# uduino-v1_1.net
KiCad netlist of a schematic drawn in EAGLE
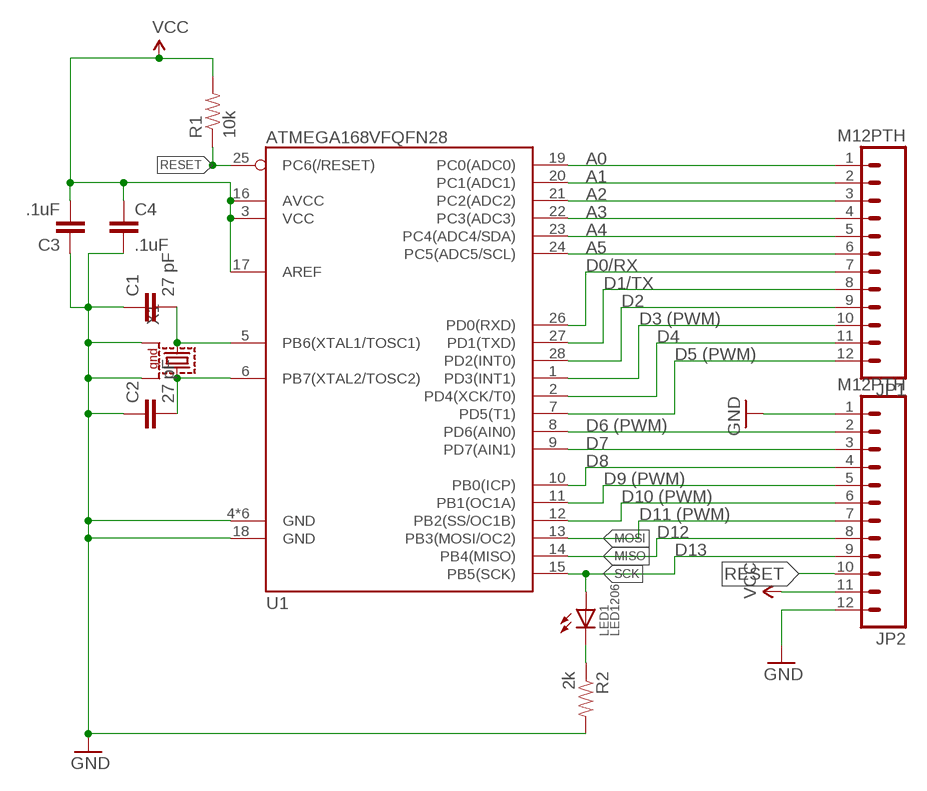
[diagram p0: schematic, sheet 1]

(export (version "E")
  (design (tool "Eeschema 10.0.6"))
  (components
    (comp (ref "C1")
      (value "27 pF")
      (footprint "eagle-import:CAP-0603")
      (libsource (lib "eagle-import") (part "CAPCAP-0603"))
    )
    (comp (ref "C2")
      (value "27 pF")
      (footprint "eagle-import:CAP-0603")
      (libsource (lib "eagle-import") (part "CAPCAP-0603"))
    )
    (comp (ref "C3")
      (value ".1uF")
      (footprint "eagle-import:CAP-0603")
      (libsource (lib "eagle-import") (part "CAPCAP-0603"))
    )
    (comp (ref "C4")
      (value ".1uF")
      (footprint "eagle-import:CAP-0603")
      (libsource (lib "eagle-import") (part "CAPCAP-0603"))
    )
    (comp (ref "JP1")
      (value "M12PTH")
      (footprint "eagle-import:1X12")
      (libsource (lib "eagle-import") (part "M12PTH"))
    )
    (comp (ref "JP2")
      (value "M12PTH")
      (footprint "eagle-import:1X12")
      (libsource (lib "eagle-import") (part "M12PTH"))
    )
    (comp (ref "LED1")
      (value "LED1206")
      (footprint "eagle-import:LED-1206")
      (libsource (lib "eagle-import") (part "LED1206"))
    )
    (comp (ref "R1")
      (value "10k")
      (footprint "eagle-import:RES-0603")
      (libsource (lib "eagle-import") (part "RESISTOR0603"))
    )
    (comp (ref "R2")
      (value "2k")
      (footprint "eagle-import:RES-0603")
      (libsource (lib "eagle-import") (part "RESISTOR0603"))
    )
    (comp (ref "U1")
      (value "ATMEGA168VFQFN28")
      (footprint "eagle-import:VQFN28")
      (libsource (lib "eagle-import") (part "ATMEGA168-28PINVFQFN-28"))
    )
    (comp (ref "X1")
      (value "CRYSTAL-SMD-7B-SERIES-TXC")
      (footprint "eagle-import:CRYSTAL-SMD-7B-SERIES-5X3.2MM")
      (fields (field (name "MFG") "TXC") (field (name "MPN") "7B SERIES"))
      (libsource (lib "eagle-import") (part "CRYSTAL-SMD-7B-SERIES-TXC"))
    )
  )
  (nets
    (net (code "1") (name "GND") (class "Default")
      (node (ref "C1") (pin "1") (pinfunction "1_1") (pintype "passive"))
      (node (ref "C2") (pin "1") (pinfunction "1_1") (pintype "passive"))
      (node (ref "C3") (pin "1") (pinfunction "1_1") (pintype "passive"))
      (node (ref "C4") (pin "2") (pinfunction "2_2") (pintype "passive"))
      (node (ref "JP2") (pin "1") (pinfunction "1_1") (pintype "passive"))
      (node (ref "JP2") (pin "12") (pinfunction "12_12") (pintype "passive"))
      (node (ref "R2") (pin "2") (pinfunction "2_2") (pintype "passive"))
      (node (ref "U1") (pin "18") (pinfunction "GND_18") (pintype "bidirectional"))
      (node (ref "U1") (pin "4") (pinfunction "GND_4") (pintype "bidirectional"))
      (node (ref "U1") (pin "TH") (pinfunction "GND_TH") (pintype "bidirectional"))
      (node (ref "U1") (pin "TH@1") (pinfunction "GND_TH@1") (pintype "bidirectional"))
      (node (ref "U1") (pin "TH@2") (pinfunction "GND_TH@2") (pintype "bidirectional"))
      (node (ref "U1") (pin "TH@3") (pinfunction "GND_TH@3") (pintype "bidirectional"))
      (node (ref "U1") (pin "TH@4") (pinfunction "GND_TH@4") (pintype "bidirectional"))
      (node (ref "X1") (pin "P$2") (pinfunction "2_P$2") (pintype "passive"))
      (node (ref "X1") (pin "P$4") (pinfunction "4_P$4") (pintype "passive"))
    )
    (net (code "2") (name "MISO") (class "Default")
      (node (ref "JP2") (pin "8") (pinfunction "8_8") (pintype "passive"))
      (node (ref "U1") (pin "14") (pinfunction "PB4(MISO)_14") (pintype "bidirectional"))
    )
    (net (code "3") (name "MOSI") (class "Default")
      (node (ref "JP2") (pin "7") (pinfunction "7_7") (pintype "passive"))
      (node (ref "U1") (pin "13") (pinfunction "PB3(MOSI/OC2)_13") (pintype "bidirectional"))
    )
    (net (code "4") (name "Net-(LED1-PadC)") (class "Default")
      (node (ref "LED1") (pin "C") (pinfunction "C_C") (pintype "passive"))
      (node (ref "R2") (pin "1") (pinfunction "1_1") (pintype "passive"))
    )
    (net (code "5") (name "Net-(U1-PB0(ICP))") (class "Default")
      (node (ref "JP2") (pin "4") (pinfunction "4_4") (pintype "passive"))
      (node (ref "U1") (pin "10") (pinfunction "PB0(ICP)_10") (pintype "bidirectional"))
    )
    (net (code "6") (name "Net-(U1-PB1(OC1A))") (class "Default")
      (node (ref "JP2") (pin "5") (pinfunction "5_5") (pintype "passive"))
      (node (ref "U1") (pin "11") (pinfunction "PB1(OC1A)_11") (pintype "bidirectional"))
    )
    (net (code "7") (name "Net-(U1-PB2(SS{slash}OC1B))") (class "Default")
      (node (ref "JP2") (pin "6") (pinfunction "6_6") (pintype "passive"))
      (node (ref "U1") (pin "12") (pinfunction "PB2(SS/OC1B)_12") (pintype "bidirectional"))
    )
    (net (code "8") (name "Net-(U1-PB6(XTAL1{slash}TOSC1))") (class "Default")
      (node (ref "C1") (pin "2") (pinfunction "2_2") (pintype "passive"))
      (node (ref "U1") (pin "5") (pinfunction "PB6(XTAL1/TOSC1)_5") (pintype "bidirectional"))
      (node (ref "X1") (pin "P$1") (pinfunction "1_P$1") (pintype "passive"))
    )
    (net (code "9") (name "Net-(U1-PB7(XTAL2{slash}TOSC2))") (class "Default")
      (node (ref "C2") (pin "2") (pinfunction "2_2") (pintype "passive"))
      (node (ref "U1") (pin "6") (pinfunction "PB7(XTAL2/TOSC2)_6") (pintype "bidirectional"))
      (node (ref "X1") (pin "P$3") (pinfunction "3_P$3") (pintype "passive"))
    )
    (net (code "10") (name "Net-(U1-PC0(ADC0))") (class "Default")
      (node (ref "JP1") (pin "1") (pinfunction "1_1") (pintype "passive"))
      (node (ref "U1") (pin "19") (pinfunction "PC0(ADC0)_19") (pintype "bidirectional"))
    )
    (net (code "11") (name "Net-(U1-PC1(ADC1))") (class "Default")
      (node (ref "JP1") (pin "2") (pinfunction "2_2") (pintype "passive"))
      (node (ref "U1") (pin "20") (pinfunction "PC1(ADC1)_20") (pintype "bidirectional"))
    )
    (net (code "12") (name "Net-(U1-PC2(ADC2))") (class "Default")
      (node (ref "JP1") (pin "3") (pinfunction "3_3") (pintype "passive"))
      (node (ref "U1") (pin "21") (pinfunction "PC2(ADC2)_21") (pintype "bidirectional"))
    )
    (net (code "13") (name "Net-(U1-PC3(ADC3))") (class "Default")
      (node (ref "JP1") (pin "4") (pinfunction "4_4") (pintype "passive"))
      (node (ref "U1") (pin "22") (pinfunction "PC3(ADC3)_22") (pintype "bidirectional"))
    )
    (net (code "14") (name "Net-(U1-PC4(ADC4{slash}SDA))") (class "Default")
      (node (ref "JP1") (pin "5") (pinfunction "5_5") (pintype "passive"))
      (node (ref "U1") (pin "23") (pinfunction "PC4(ADC4/SDA)_23") (pintype "bidirectional"))
    )
    (net (code "15") (name "Net-(U1-PC5(ADC5{slash}SCL))") (class "Default")
      (node (ref "JP1") (pin "6") (pinfunction "6_6") (pintype "passive"))
      (node (ref "U1") (pin "24") (pinfunction "PC5(ADC5/SCL)_24") (pintype "bidirectional"))
    )
    (net (code "16") (name "Net-(U1-PD0(RXD))") (class "Default")
      (node (ref "JP1") (pin "7") (pinfunction "7_7") (pintype "passive"))
      (node (ref "U1") (pin "26") (pinfunction "PD0(RXD)_26") (pintype "bidirectional"))
    )
    (net (code "17") (name "Net-(U1-PD1(TXD))") (class "Default")
      (node (ref "JP1") (pin "8") (pinfunction "8_8") (pintype "passive"))
      (node (ref "U1") (pin "27") (pinfunction "PD1(TXD)_27") (pintype "bidirectional"))
    )
    (net (code "18") (name "Net-(U1-PD2(INT0))") (class "Default")
      (node (ref "JP1") (pin "9") (pinfunction "9_9") (pintype "passive"))
      (node (ref "U1") (pin "28") (pinfunction "PD2(INT0)_28") (pintype "bidirectional"))
    )
    (net (code "19") (name "Net-(U1-PD3(INT1))") (class "Default")
      (node (ref "JP1") (pin "10") (pinfunction "10_10") (pintype "passive"))
      (node (ref "U1") (pin "1") (pinfunction "PD3(INT1)_1") (pintype "bidirectional"))
    )
    (net (code "20") (name "Net-(U1-PD4(XCK{slash}T0))") (class "Default")
      (node (ref "JP1") (pin "11") (pinfunction "11_11") (pintype "passive"))
      (node (ref "U1") (pin "2") (pinfunction "PD4(XCK/T0)_2") (pintype "bidirectional"))
    )
    (net (code "21") (name "Net-(U1-PD5(T1))") (class "Default")
      (node (ref "JP1") (pin "12") (pinfunction "12_12") (pintype "passive"))
      (node (ref "U1") (pin "7") (pinfunction "PD5(T1)_7") (pintype "bidirectional"))
    )
    (net (code "22") (name "Net-(U1-PD6(AIN0))") (class "Default")
      (node (ref "JP2") (pin "2") (pinfunction "2_2") (pintype "passive"))
      (node (ref "U1") (pin "8") (pinfunction "PD6(AIN0)_8") (pintype "bidirectional"))
    )
    (net (code "23") (name "Net-(U1-PD7(AIN1))") (class "Default")
      (node (ref "JP2") (pin "3") (pinfunction "3_3") (pintype "passive"))
      (node (ref "U1") (pin "9") (pinfunction "PD7(AIN1)_9") (pintype "bidirectional"))
    )
    (net (code "24") (name "RESET") (class "Default")
      (node (ref "JP2") (pin "10") (pinfunction "10_10") (pintype "passive"))
      (node (ref "R1") (pin "1") (pinfunction "1_1") (pintype "passive"))
      (node (ref "U1") (pin "25") (pinfunction "PC6(/RESET)_25") (pintype "bidirectional"))
    )
    (net (code "25") (name "SCK") (class "Default")
      (node (ref "JP2") (pin "9") (pinfunction "9_9") (pintype "passive"))
      (node (ref "LED1") (pin "A") (pinfunction "A_A") (pintype "passive"))
      (node (ref "U1") (pin "15") (pinfunction "PB5(SCK)_15") (pintype "bidirectional"))
    )
    (net (code "26") (name "VCC") (class "Default")
      (node (ref "C3") (pin "2") (pinfunction "2_2") (pintype "passive"))
      (node (ref "C4") (pin "1") (pinfunction "1_1") (pintype "passive"))
      (node (ref "JP2") (pin "11") (pinfunction "11_11") (pintype "passive"))
      (node (ref "R1") (pin "2") (pinfunction "2_2") (pintype "passive"))
      (node (ref "U1") (pin "16") (pinfunction "AVCC_16") (pintype "bidirectional"))
      (node (ref "U1") (pin "17") (pinfunction "AREF_17") (pintype "bidirectional"))
      (node (ref "U1") (pin "3") (pinfunction "VCC_3") (pintype "bidirectional"))
    )
  )
)
